# RS485_FD.net
KiCad netlist of a schematic drawn in Altium Designer
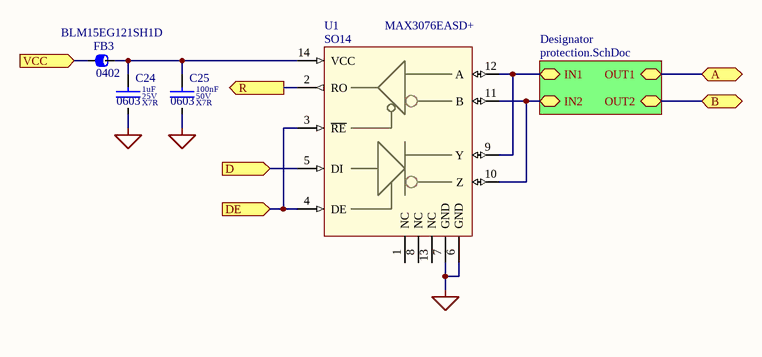
[diagram p0: RS485_FD.SchDoc]

(export (version "E")
  (design (tool "Eeschema 10.0.6"))
  (components
    (comp (ref "C24")
      (value "1uF")
      (footprint "C_0603_1608")
      (description "Capacitor")
      (fields
        (field (name "DIELECTRIC") "X7R")
        (field (name "VOLTAGE") "25V")
        (field (name "SCH_FOOTPRINT") "0603")
        (field (name "PART NUMBER") "C_1uF_25V_X7R_0603_10")
        (field (name "MANUFACTURER") "Samsung")
      )
      (libsource (lib "Library") (part "C"))
    )
    (comp (ref "C25")
      (value "100nF")
      (footprint "C_0603_1608")
      (description "Capacitor")
      (fields
        (field (name "DIELECTRIC") "X7R")
        (field (name "VOLTAGE") "50V")
        (field (name "SCH_FOOTPRINT") "0603")
        (field (name "PART NUMBER") "C_100nF_50V_X7R_0603_5")
        (field (name "MANUFACTURER") "Samsung")
      )
      (libsource (lib "Library") (part "C"))
    )
    (comp (ref "FB3")
      (value "Ferrite bead")
      (footprint "FB_0402_1005")
      (description "Ferrite Bead")
      (fields
        (field (name "PART NUMBER") "FB_BLM15EG121SH1D")
        (field (name "SCH_FOOTPRINT") "0402")
        (field (name "MANUFACTURER") "Murata")
        (field (name "MANUFACTURER PART NUMBER") "BLM15EG121SH1D")
      )
      (libsource (lib "Library") (part "FB"))
    )
    (comp (ref "U1")
      (value "MAX3076EASD+")
      (footprint "SOP14_SO14_SOIC14_4X9X18")
      (description "RS-485/RS-422 Transceivers, +3.3V,  ±15kV ESD-Protected, Fail-Safe, Hot-Swap")
      (fields
        (field (name "SCH_FOOTPRINT") "SO14")
        (field (name "PART NUMBER") "U_MAX3076EASD+")
        (field (name "MANUFACTURER") "Maxim Integrated")
      )
      (libsource (lib "Library") (part "U_MAX3076E"))
    )
  )
  (nets
    (net (code "3") (name "/D") (class "Default")
      (node (ref "U1") (pin "5") (pinfunction "DI_5") (pintype "input"))
    )
    (net (code "4") (name "/DE") (class "Default")
      (node (ref "U1") (pin "3") (pinfunction "~{RE}_3") (pintype "input"))
      (node (ref "U1") (pin "4") (pinfunction "DE_4") (pintype "input"))
    )
    (net (code "5") (name "/IN1") (class "Default")
      (node (ref "U1") (pin "12") (pinfunction "A_12") (pintype "bidirectional"))
      (node (ref "U1") (pin "9") (pinfunction "Y_9") (pintype "bidirectional"))
    )
    (net (code "6") (name "/IN2") (class "Default")
      (node (ref "U1") (pin "10") (pinfunction "Z_10") (pintype "bidirectional"))
      (node (ref "U1") (pin "11") (pinfunction "B_11") (pintype "bidirectional"))
    )
    (net (code "7") (name "/R") (class "Default")
      (node (ref "U1") (pin "2") (pinfunction "RO_2") (pintype "output"))
    )
    (net (code "8") (name "/VCC") (class "Default") (node (ref "FB3") (pin "1") (pintype "input")))
    (net (code "9") (name "GND") (class "Default")
      (node (ref "C24") (pin "2") (pinfunction "2_2") (pintype "passive"))
      (node (ref "C25") (pin "2") (pinfunction "2_2") (pintype "passive"))
      (node (ref "U1") (pin "6") (pinfunction "GND_6") (pintype "power_in"))
      (node (ref "U1") (pin "7") (pinfunction "GND_7") (pintype "power_in"))
    )
    (net (code "10") (name "Net-(U1-VCC)") (class "Default")
      (node (ref "C24") (pin "1") (pinfunction "1_1") (pintype "passive"))
      (node (ref "C25") (pin "1") (pinfunction "1_1") (pintype "passive"))
      (node (ref "FB3") (pin "2") (pintype "output"))
      (node (ref "U1") (pin "14") (pinfunction "VCC_14") (pintype "input"))
    )
    (net (code "11") (name "unconnected-(U1-NC-Pad1)") (class "Default")
      (node (ref "U1") (pin "1") (pinfunction "NC_1") (pintype "passive"))
    )
    (net (code "12") (name "unconnected-(U1-NC-Pad8)") (class "Default")
      (node (ref "U1") (pin "8") (pinfunction "NC_8") (pintype "passive"))
    )
    (net (code "13") (name "unconnected-(U1-NC-Pad13)") (class "Default")
      (node (ref "U1") (pin "13") (pinfunction "NC_13") (pintype "passive"))
    )
  )
)
